# spectrometer-shield.net
KiCad netlist of a schematic drawn in EAGLE
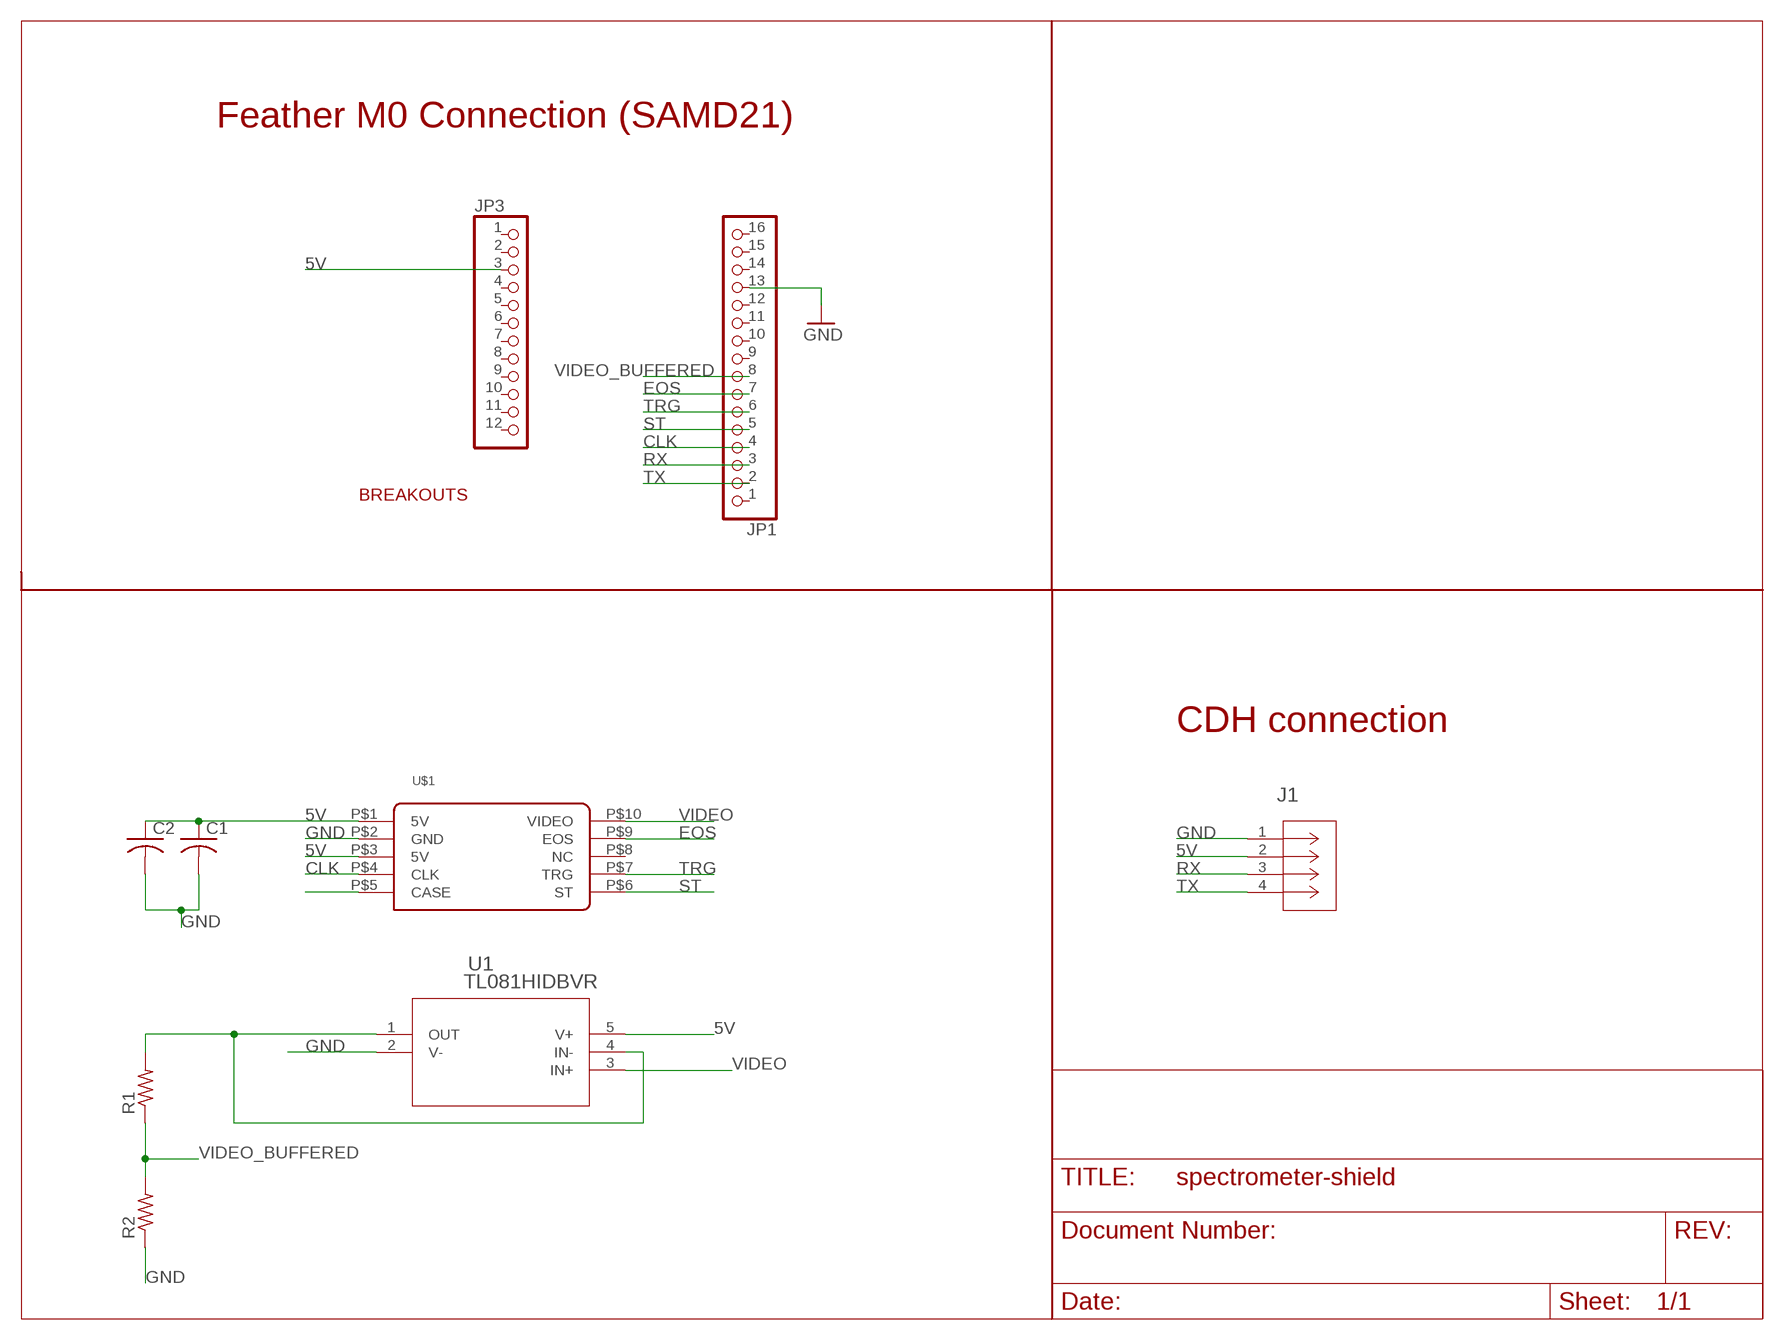
[diagram p0: schematic, sheet 1]

(export (version "E")
  (design (tool "Eeschema 10.0.6"))
  (components
    (comp (ref "C1")
      (value "C-USC1206")
      (footprint "eagle-import:C1206")
      (libsource (lib "eagle-import") (part "C-USC1206"))
    )
    (comp (ref "C2")
      (value "C-USC0603")
      (footprint "eagle-import:C0603")
      (libsource (lib "eagle-import") (part "C-USC0603"))
    )
    (comp (ref "J1")
      (value "S4B-PH-SM4-TB(LF)(SN)")
      (footprint "eagle-import:CONN_S4B-PH-SM4-TB(LF)(SN)_JST")
      (fields (field (name "COPYRIGHT") "Copyright (C) 2022 Ultra Librarian. All rights reserved."))
      (libsource (lib "eagle-import") (part "S4B-PH-SM4-TB(LF)(SN)"))
    )
    (comp (ref "JP1")
      (value "HEADER-1X16ROUND")
      (footprint "eagle-import:1X16_ROUND")
      (libsource (lib "eagle-import") (part "HEADER-1X16ROUND"))
    )
    (comp (ref "JP3")
      (value "HEADER-1X12")
      (footprint "eagle-import:1X12_ROUND")
      (libsource (lib "eagle-import") (part "HEADER-1X12"))
    )
    (comp (ref "R1")
      (value "R-US_R0603")
      (footprint "eagle-import:R0603")
      (libsource (lib "eagle-import") (part "R-US_R0603"))
    )
    (comp (ref "R2")
      (value "R-US_R0603")
      (footprint "eagle-import:R0603")
      (libsource (lib "eagle-import") (part "R-US_R0603"))
    )
    (comp (ref "U$1")
      (value "C12880MA")
      (footprint "eagle-import:C12880MA_FOOTPRINT")
      (libsource (lib "eagle-import") (part "C12880MA"))
    )
    (comp (ref "U1")
      (value "TL081HIDBVR")
      (footprint "eagle-import:SOT-23-5_DBV_TEX")
      (fields (field (name "COPYRIGHT") "Copyright (C) 2022 Ultra Librarian. All rights reserved."))
      (libsource (lib "eagle-import") (part "TL081HIDBVR"))
    )
  )
  (nets
    (net (code "1") (name "/5V") (class "Default")
      (node (ref "C1") (pin "1") (pinfunction "1_1") (pintype "passive"))
      (node (ref "C2") (pin "1") (pinfunction "1_1") (pintype "passive"))
      (node (ref "J1") (pin "2") (pinfunction "2_2") (pintype "passive"))
      (node (ref "JP3") (pin "3") (pinfunction "3_3") (pintype "passive"))
      (node (ref "U$1") (pin "P$1") (pinfunction "5V_P$1") (pintype "bidirectional"))
      (node (ref "U$1") (pin "P$3") (pinfunction "5V_P$3") (pintype "bidirectional"))
      (node (ref "U1") (pin "5") (pinfunction "V+_5") (pintype "power_in"))
    )
    (net (code "2") (name "/CLK") (class "Default")
      (node (ref "JP1") (pin "4") (pinfunction "4_4") (pintype "passive"))
      (node (ref "U$1") (pin "P$4") (pinfunction "CLK_P$4") (pintype "bidirectional"))
    )
    (net (code "3") (name "/EOS") (class "Default")
      (node (ref "JP1") (pin "7") (pinfunction "7_7") (pintype "passive"))
      (node (ref "U$1") (pin "P$9") (pinfunction "EOS_P$9") (pintype "bidirectional"))
    )
    (net (code "4") (name "/RX") (class "Default")
      (node (ref "J1") (pin "3") (pinfunction "3_3") (pintype "passive"))
      (node (ref "JP1") (pin "3") (pinfunction "3_3") (pintype "passive"))
    )
    (net (code "5") (name "/ST") (class "Default")
      (node (ref "JP1") (pin "5") (pinfunction "5_5") (pintype "passive"))
      (node (ref "U$1") (pin "P$6") (pinfunction "ST_P$6") (pintype "bidirectional"))
    )
    (net (code "6") (name "/TRG") (class "Default")
      (node (ref "JP1") (pin "6") (pinfunction "6_6") (pintype "passive"))
      (node (ref "U$1") (pin "P$7") (pinfunction "TRG_P$7") (pintype "bidirectional"))
    )
    (net (code "7") (name "/TX") (class "Default")
      (node (ref "J1") (pin "4") (pinfunction "4_4") (pintype "passive"))
      (node (ref "JP1") (pin "2") (pinfunction "2_2") (pintype "passive"))
    )
    (net (code "8") (name "/VIDEO") (class "Default")
      (node (ref "U$1") (pin "P$10") (pinfunction "VIDEO_P$10") (pintype "bidirectional"))
      (node (ref "U1") (pin "3") (pinfunction "IN+_3") (pintype "input"))
    )
    (net (code "9") (name "/VIDEO_BUFFERED") (class "Default")
      (node (ref "JP1") (pin "8") (pinfunction "8_8") (pintype "passive"))
      (node (ref "R1") (pin "1") (pinfunction "1_1") (pintype "passive"))
      (node (ref "R2") (pin "2") (pinfunction "2_2") (pintype "passive"))
    )
    (net (code "10") (name "GND") (class "Default")
      (node (ref "C1") (pin "2") (pinfunction "2_2") (pintype "passive"))
      (node (ref "C2") (pin "2") (pinfunction "2_2") (pintype "passive"))
      (node (ref "J1") (pin "1") (pinfunction "1_1") (pintype "passive"))
      (node (ref "JP1") (pin "13") (pinfunction "13_13") (pintype "passive"))
      (node (ref "R2") (pin "1") (pinfunction "1_1") (pintype "passive"))
      (node (ref "U$1") (pin "P$2") (pinfunction "GND_P$2") (pintype "bidirectional"))
      (node (ref "U$1") (pin "P$5") (pinfunction "CASE_P$5") (pintype "bidirectional"))
      (node (ref "U1") (pin "2") (pinfunction "V-_2") (pintype "power_in"))
    )
    (net (code "11") (name "Net-(U1-IN-)") (class "Default")
      (node (ref "R1") (pin "2") (pinfunction "2_2") (pintype "passive"))
      (node (ref "U1") (pin "1") (pinfunction "OUT_1") (pintype "output"))
      (node (ref "U1") (pin "4") (pinfunction "IN-_4") (pintype "input"))
    )
    (net (code "12") (name "unconnected-(JP1-Pad1)") (class "Default")
      (node (ref "JP1") (pin "1") (pinfunction "1_1") (pintype "passive"))
    )
    (net (code "13") (name "unconnected-(JP1-Pad9)") (class "Default")
      (node (ref "JP1") (pin "9") (pinfunction "9_9") (pintype "passive"))
    )
    (net (code "14") (name "unconnected-(JP1-Pad10)") (class "Default")
      (node (ref "JP1") (pin "10") (pinfunction "10_10") (pintype "passive"))
    )
    (net (code "15") (name "unconnected-(JP1-Pad11)") (class "Default")
      (node (ref "JP1") (pin "11") (pinfunction "11_11") (pintype "passive"))
    )
    (net (code "16") (name "unconnected-(JP1-Pad12)") (class "Default")
      (node (ref "JP1") (pin "12") (pinfunction "12_12") (pintype "passive"))
    )
    (net (code "17") (name "unconnected-(JP1-Pad14)") (class "Default")
      (node (ref "JP1") (pin "14") (pinfunction "14_14") (pintype "passive"))
    )
    (net (code "18") (name "unconnected-(JP1-Pad15)") (class "Default")
      (node (ref "JP1") (pin "15") (pinfunction "15_15") (pintype "passive"))
    )
    (net (code "19") (name "unconnected-(JP1-Pad16)") (class "Default")
      (node (ref "JP1") (pin "16") (pinfunction "16_16") (pintype "passive"))
    )
    (net (code "20") (name "unconnected-(JP3-Pad1)") (class "Default")
      (node (ref "JP3") (pin "1") (pinfunction "1_1") (pintype "passive"))
    )
    (net (code "21") (name "unconnected-(JP3-Pad2)") (class "Default")
      (node (ref "JP3") (pin "2") (pinfunction "2_2") (pintype "passive"))
    )
    (net (code "22") (name "unconnected-(JP3-Pad4)") (class "Default")
      (node (ref "JP3") (pin "4") (pinfunction "4_4") (pintype "passive"))
    )
    (net (code "23") (name "unconnected-(JP3-Pad5)") (class "Default")
      (node (ref "JP3") (pin "5") (pinfunction "5_5") (pintype "passive"))
    )
    (net (code "24") (name "unconnected-(JP3-Pad6)") (class "Default")
      (node (ref "JP3") (pin "6") (pinfunction "6_6") (pintype "passive"))
    )
    (net (code "25") (name "unconnected-(JP3-Pad7)") (class "Default")
      (node (ref "JP3") (pin "7") (pinfunction "7_7") (pintype "passive"))
    )
    (net (code "26") (name "unconnected-(JP3-Pad8)") (class "Default")
      (node (ref "JP3") (pin "8") (pinfunction "8_8") (pintype "passive"))
    )
    (net (code "27") (name "unconnected-(JP3-Pad9)") (class "Default")
      (node (ref "JP3") (pin "9") (pinfunction "9_9") (pintype "passive"))
    )
    (net (code "28") (name "unconnected-(JP3-Pad10)") (class "Default")
      (node (ref "JP3") (pin "10") (pinfunction "10_10") (pintype "passive"))
    )
    (net (code "29") (name "unconnected-(JP3-Pad11)") (class "Default")
      (node (ref "JP3") (pin "11") (pinfunction "11_11") (pintype "passive"))
    )
    (net (code "30") (name "unconnected-(JP3-Pad12)") (class "Default")
      (node (ref "JP3") (pin "12") (pinfunction "12_12") (pintype "passive"))
    )
    (net (code "31") (name "unconnected-(U$1-NC-PadP$8)") (class "Default")
      (node (ref "U$1") (pin "P$8") (pinfunction "NC_P$8") (pintype "bidirectional"))
    )
  )
)
